# od808_redraw.net
KiCad netlist of a schematic drawn in EAGLE
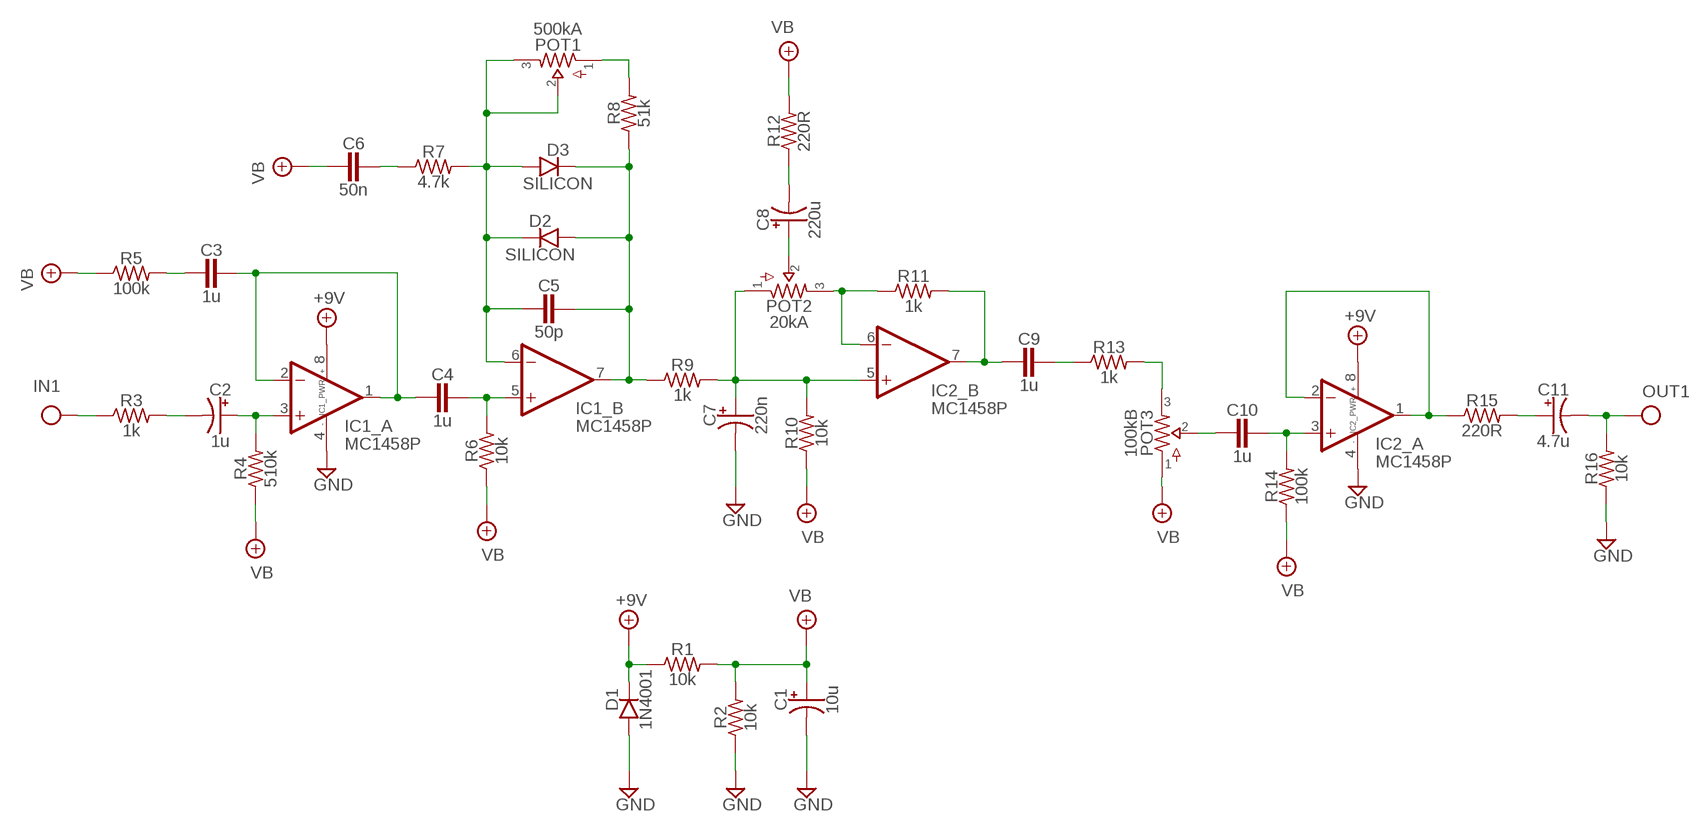
[diagram p0: schematic, sheet 1]

(export (version "E")
  (design (tool "Eeschema 10.0.6"))
  (components
    (comp (ref "C1")
      (value "10u")
      (footprint "eagle-import:050_020")
      (libsource (lib "eagle-import") (part "0500"))
    )
    (comp (ref "C2")
      (value "1u")
      (footprint "eagle-import:050_020")
      (libsource (lib "eagle-import") (part "0500"))
    )
    (comp (ref "C3")
      (value "1u")
      (footprint "eagle-import:BOX_SMALL")
      (libsource (lib "eagle-import") (part "CER/FILMBOX.1"))
    )
    (comp (ref "C4")
      (value "1u")
      (footprint "eagle-import:BOX_SMALL")
      (libsource (lib "eagle-import") (part "CER/FILMBOX.1"))
    )
    (comp (ref "C5")
      (value "50p")
      (footprint "eagle-import:BOX_SMALL")
      (libsource (lib "eagle-import") (part "CER/FILMBOX.1"))
    )
    (comp (ref "C6")
      (value "50n")
      (footprint "eagle-import:BOX_SMALL")
      (libsource (lib "eagle-import") (part "CER/FILMBOX.1"))
    )
    (comp (ref "C7")
      (value "220n")
      (footprint "eagle-import:050_020")
      (libsource (lib "eagle-import") (part "0500"))
    )
    (comp (ref "C8")
      (value "220u")
      (footprint "eagle-import:050_020")
      (libsource (lib "eagle-import") (part "0500"))
    )
    (comp (ref "C9")
      (value "1u")
      (footprint "eagle-import:BOX_SMALL")
      (libsource (lib "eagle-import") (part "CER/FILMBOX.1"))
    )
    (comp (ref "C10")
      (value "1u")
      (footprint "eagle-import:BOX_SMALL")
      (libsource (lib "eagle-import") (part "CER/FILMBOX.1"))
    )
    (comp (ref "C11")
      (value "4.7u")
      (footprint "eagle-import:050_020")
      (libsource (lib "eagle-import") (part "0500"))
    )
    (comp (ref "D1")
      (value "1N4001")
      (footprint "eagle-import:DO35-2")
      (libsource (lib "eagle-import") (part "DO35.2"))
    )
    (comp (ref "D2")
      (value "SILICON")
      (footprint "eagle-import:DO35-2")
      (libsource (lib "eagle-import") (part "DO35.2"))
    )
    (comp (ref "D3")
      (value "SILICON")
      (footprint "eagle-import:DO35-2")
      (libsource (lib "eagle-import") (part "DO35.2"))
    )
    (comp (ref "IC1")
      (value "MC1458P")
      (footprint "eagle-import:DIL0")
      (libsource (lib "eagle-import") (part "DUALTH"))
    )
    (comp (ref "IC2")
      (value "MC1458P")
      (footprint "eagle-import:DIL0")
      (libsource (lib "eagle-import") (part "DUALTH"))
    )
    (comp (ref "POT1")
      (value "500kA")
      (footprint "eagle-import:16MM")
      (libsource (lib "eagle-import") (part "POTS16MM"))
    )
    (comp (ref "POT2")
      (value "20kA")
      (footprint "eagle-import:16MM")
      (libsource (lib "eagle-import") (part "POTS16MM"))
    )
    (comp (ref "POT3")
      (value "100kB")
      (footprint "eagle-import:16MM")
      (libsource (lib "eagle-import") (part "POTS16MM"))
    )
    (comp (ref "R1")
      (value "10k")
      (footprint "eagle-import:R0207_3")
      (libsource (lib "eagle-import") (part "R_.3B"))
    )
    (comp (ref "R2")
      (value "10k")
      (footprint "eagle-import:R0207_3")
      (libsource (lib "eagle-import") (part "R_.3B"))
    )
    (comp (ref "R3")
      (value "1k")
      (footprint "eagle-import:R0207_3")
      (libsource (lib "eagle-import") (part "R_.3B"))
    )
    (comp (ref "R4")
      (value "510k")
      (footprint "eagle-import:R0207_3")
      (libsource (lib "eagle-import") (part "R_.3B"))
    )
    (comp (ref "R5")
      (value "100k")
      (footprint "eagle-import:R0207_3")
      (libsource (lib "eagle-import") (part "R_.3B"))
    )
    (comp (ref "R6")
      (value "10k")
      (footprint "eagle-import:R0207_3")
      (libsource (lib "eagle-import") (part "R_.3B"))
    )
    (comp (ref "R7")
      (value "4.7k")
      (footprint "eagle-import:R0207_3")
      (libsource (lib "eagle-import") (part "R_.3B"))
    )
    (comp (ref "R8")
      (value "51k")
      (footprint "eagle-import:R0207_3")
      (libsource (lib "eagle-import") (part "R_.3B"))
    )
    (comp (ref "R9")
      (value "1k")
      (footprint "eagle-import:R0207_3")
      (libsource (lib "eagle-import") (part "R_.3B"))
    )
    (comp (ref "R10")
      (value "10k")
      (footprint "eagle-import:R0207_3")
      (libsource (lib "eagle-import") (part "R_.3B"))
    )
    (comp (ref "R11")
      (value "1k")
      (footprint "eagle-import:R0207_3")
      (libsource (lib "eagle-import") (part "R_.3B"))
    )
    (comp (ref "R12")
      (value "220R")
      (footprint "eagle-import:R0207_3")
      (libsource (lib "eagle-import") (part "R_.3B"))
    )
    (comp (ref "R13")
      (value "1k")
      (footprint "eagle-import:R0207_3")
      (libsource (lib "eagle-import") (part "R_.3B"))
    )
    (comp (ref "R14")
      (value "100k")
      (footprint "eagle-import:R0207_3")
      (libsource (lib "eagle-import") (part "R_.3B"))
    )
    (comp (ref "R15")
      (value "220R")
      (footprint "eagle-import:R0207_3")
      (libsource (lib "eagle-import") (part "R_.3B"))
    )
    (comp (ref "R16")
      (value "10k")
      (footprint "eagle-import:R0207_3")
      (libsource (lib "eagle-import") (part "R_.3B"))
    )
  )
  (nets
    (net (code "1") (name "+9V") (class "Default")
      (node (ref "D1") (pin "C") (pinfunction "C_C") (pintype "passive"))
      (node (ref "IC1") (pin "8") (pinfunction "V+_8") (pintype "power_in"))
      (node (ref "IC2") (pin "8") (pinfunction "V+_8") (pintype "power_in"))
      (node (ref "R1") (pin "1") (pinfunction "1_1") (pintype "passive"))
    )
    (net (code "2") (name "GND") (class "Default")
      (node (ref "C1") (pin "-") (pinfunction "-_-") (pintype "passive"))
      (node (ref "C7") (pin "-") (pinfunction "-_-") (pintype "passive"))
      (node (ref "D1") (pin "A") (pinfunction "A_A") (pintype "passive"))
      (node (ref "IC1") (pin "4") (pinfunction "V-_4") (pintype "power_in"))
      (node (ref "IC2") (pin "4") (pinfunction "V-_4") (pintype "power_in"))
      (node (ref "R16") (pin "1") (pinfunction "1_1") (pintype "passive"))
      (node (ref "R2") (pin "1") (pinfunction "1_1") (pintype "passive"))
    )
    (net (code "3") (name "IN") (class "Default")
      (node (ref "R3") (pin "1") (pinfunction "1_1") (pintype "passive"))
    )
    (net (code "4") (name "Net-(C2-Pad-)") (class "Default")
      (node (ref "C2") (pin "-") (pinfunction "-_-") (pintype "passive"))
      (node (ref "R3") (pin "2") (pinfunction "2_2") (pintype "passive"))
    )
    (net (code "5") (name "Net-(C3-Pad2)") (class "Default")
      (node (ref "C3") (pin "2") (pinfunction "2_2") (pintype "passive"))
      (node (ref "R5") (pin "2") (pinfunction "2_2") (pintype "passive"))
    )
    (net (code "6") (name "Net-(C6-Pad1)") (class "Default")
      (node (ref "C6") (pin "1") (pinfunction "1_1") (pintype "passive"))
      (node (ref "R7") (pin "1") (pinfunction "1_1") (pintype "passive"))
    )
    (net (code "7") (name "Net-(C8-Pad+)") (class "Default")
      (node (ref "C8") (pin "+") (pinfunction "+_+") (pintype "passive"))
      (node (ref "POT2") (pin "2") (pinfunction "2_2") (pintype "passive"))
    )
    (net (code "8") (name "Net-(C8-Pad-)") (class "Default")
      (node (ref "C8") (pin "-") (pinfunction "-_-") (pintype "passive"))
      (node (ref "R12") (pin "1") (pinfunction "1_1") (pintype "passive"))
    )
    (net (code "9") (name "Net-(C9-Pad1)") (class "Default")
      (node (ref "C9") (pin "1") (pinfunction "1_1") (pintype "passive"))
      (node (ref "R13") (pin "1") (pinfunction "1_1") (pintype "passive"))
    )
    (net (code "10") (name "Net-(C10-Pad2)") (class "Default")
      (node (ref "C10") (pin "2") (pinfunction "2_2") (pintype "passive"))
      (node (ref "POT3") (pin "2") (pinfunction "2_2") (pintype "passive"))
    )
    (net (code "11") (name "Net-(C11-Pad+)") (class "Default")
      (node (ref "C11") (pin "+") (pinfunction "+_+") (pintype "passive"))
      (node (ref "R15") (pin "2") (pinfunction "2_2") (pintype "passive"))
    )
    (net (code "12") (name "Net-(IC1A-+IN)") (class "Default")
      (node (ref "C2") (pin "+") (pinfunction "+_+") (pintype "passive"))
      (node (ref "IC1") (pin "3") (pinfunction "+IN_3") (pintype "input"))
      (node (ref "R4") (pin "2") (pinfunction "2_2") (pintype "passive"))
    )
    (net (code "13") (name "Net-(IC1A--IN)") (class "Default")
      (node (ref "C3") (pin "1") (pinfunction "1_1") (pintype "passive"))
      (node (ref "C4") (pin "2") (pinfunction "2_2") (pintype "passive"))
      (node (ref "IC1") (pin "1") (pinfunction "OUT_1") (pintype "output"))
      (node (ref "IC1") (pin "2") (pinfunction "-IN_2") (pintype "input"))
    )
    (net (code "14") (name "Net-(IC1B-+IN)") (class "Default")
      (node (ref "C4") (pin "1") (pinfunction "1_1") (pintype "passive"))
      (node (ref "IC1") (pin "5") (pinfunction "+IN_5") (pintype "input"))
      (node (ref "R6") (pin "2") (pinfunction "2_2") (pintype "passive"))
    )
    (net (code "15") (name "Net-(IC1B--IN)") (class "Default")
      (node (ref "C5") (pin "2") (pinfunction "2_2") (pintype "passive"))
      (node (ref "D2") (pin "C") (pinfunction "C_C") (pintype "passive"))
      (node (ref "D3") (pin "A") (pinfunction "A_A") (pintype "passive"))
      (node (ref "IC1") (pin "6") (pinfunction "-IN_6") (pintype "input"))
      (node (ref "POT1") (pin "2") (pinfunction "2_2") (pintype "passive"))
      (node (ref "POT1") (pin "3") (pinfunction "3_3") (pintype "passive"))
      (node (ref "R7") (pin "2") (pinfunction "2_2") (pintype "passive"))
    )
    (net (code "16") (name "Net-(IC1B-OUT)") (class "Default")
      (node (ref "C5") (pin "1") (pinfunction "1_1") (pintype "passive"))
      (node (ref "D2") (pin "A") (pinfunction "A_A") (pintype "passive"))
      (node (ref "D3") (pin "C") (pinfunction "C_C") (pintype "passive"))
      (node (ref "IC1") (pin "7") (pinfunction "OUT_7") (pintype "output"))
      (node (ref "R8") (pin "1") (pinfunction "1_1") (pintype "passive"))
      (node (ref "R9") (pin "1") (pinfunction "1_1") (pintype "passive"))
    )
    (net (code "17") (name "Net-(IC2A-+IN)") (class "Default")
      (node (ref "C10") (pin "1") (pinfunction "1_1") (pintype "passive"))
      (node (ref "IC2") (pin "3") (pinfunction "+IN_3") (pintype "input"))
      (node (ref "R14") (pin "2") (pinfunction "2_2") (pintype "passive"))
    )
    (net (code "18") (name "Net-(IC2A--IN)") (class "Default")
      (node (ref "IC2") (pin "1") (pinfunction "OUT_1") (pintype "output"))
      (node (ref "IC2") (pin "2") (pinfunction "-IN_2") (pintype "input"))
      (node (ref "R15") (pin "1") (pinfunction "1_1") (pintype "passive"))
    )
    (net (code "19") (name "Net-(IC2B-+IN)") (class "Default")
      (node (ref "C7") (pin "+") (pinfunction "+_+") (pintype "passive"))
      (node (ref "IC2") (pin "5") (pinfunction "+IN_5") (pintype "input"))
      (node (ref "POT2") (pin "1") (pinfunction "1_1") (pintype "passive"))
      (node (ref "R10") (pin "2") (pinfunction "2_2") (pintype "passive"))
      (node (ref "R9") (pin "2") (pinfunction "2_2") (pintype "passive"))
    )
    (net (code "20") (name "Net-(IC2B--IN)") (class "Default")
      (node (ref "IC2") (pin "6") (pinfunction "-IN_6") (pintype "input"))
      (node (ref "POT2") (pin "3") (pinfunction "3_3") (pintype "passive"))
      (node (ref "R11") (pin "1") (pinfunction "1_1") (pintype "passive"))
    )
    (net (code "21") (name "Net-(IC2B-OUT)") (class "Default")
      (node (ref "C9") (pin "2") (pinfunction "2_2") (pintype "passive"))
      (node (ref "IC2") (pin "7") (pinfunction "OUT_7") (pintype "output"))
      (node (ref "R11") (pin "2") (pinfunction "2_2") (pintype "passive"))
    )
    (net (code "22") (name "Net-(POT1-Pad1)") (class "Default")
      (node (ref "POT1") (pin "1") (pinfunction "1_1") (pintype "passive"))
      (node (ref "R8") (pin "2") (pinfunction "2_2") (pintype "passive"))
    )
    (net (code "23") (name "Net-(POT3-Pad3)") (class "Default")
      (node (ref "POT3") (pin "3") (pinfunction "3_3") (pintype "passive"))
      (node (ref "R13") (pin "2") (pinfunction "2_2") (pintype "passive"))
    )
    (net (code "24") (name "OUT") (class "Default")
      (node (ref "C11") (pin "-") (pinfunction "-_-") (pintype "passive"))
      (node (ref "R16") (pin "2") (pinfunction "2_2") (pintype "passive"))
    )
    (net (code "25") (name "VB") (class "Default")
      (node (ref "C1") (pin "+") (pinfunction "+_+") (pintype "passive"))
      (node (ref "C6") (pin "2") (pinfunction "2_2") (pintype "passive"))
      (node (ref "POT3") (pin "1") (pinfunction "1_1") (pintype "passive"))
      (node (ref "R1") (pin "2") (pinfunction "2_2") (pintype "passive"))
      (node (ref "R10") (pin "1") (pinfunction "1_1") (pintype "passive"))
      (node (ref "R12") (pin "2") (pinfunction "2_2") (pintype "passive"))
      (node (ref "R14") (pin "1") (pinfunction "1_1") (pintype "passive"))
      (node (ref "R2") (pin "2") (pinfunction "2_2") (pintype "passive"))
      (node (ref "R4") (pin "1") (pinfunction "1_1") (pintype "passive"))
      (node (ref "R5") (pin "1") (pinfunction "1_1") (pintype "passive"))
      (node (ref "R6") (pin "1") (pinfunction "1_1") (pintype "passive"))
    )
  )
)
